# 11_INPUT.net
KiCad netlist of a schematic drawn in Altium Designer
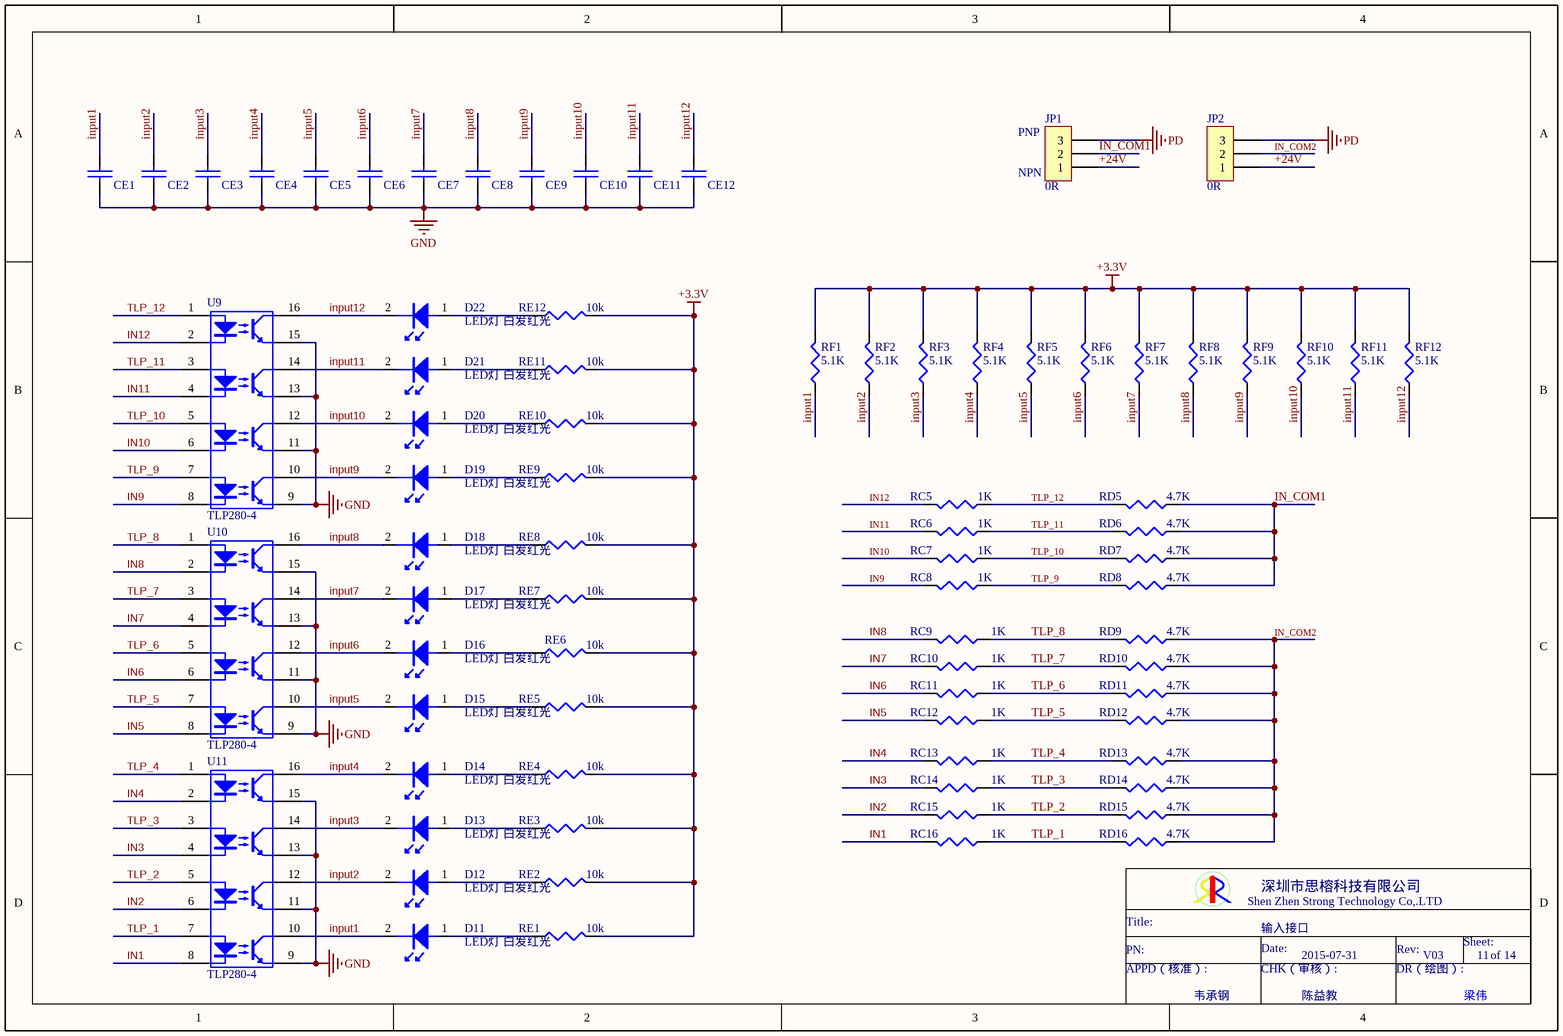
[diagram p0: 11_INPUT.SchDoc]

(export (version "E")
  (design (tool "Eeschema 10.0.6"))
  (components
    (comp (ref "CE1")
      (value "100pF")
      (footprint "0603C")
      (description "Capacitor")
      (libsource (lib "Mylibrary") (part "CAP"))
    )
    (comp (ref "CE2")
      (value "100pF")
      (footprint "0603C")
      (description "Capacitor")
      (libsource (lib "Mylibrary") (part "CAP"))
    )
    (comp (ref "CE3")
      (value "100pF")
      (footprint "0603C")
      (description "Capacitor")
      (libsource (lib "Mylibrary") (part "CAP"))
    )
    (comp (ref "CE4")
      (value "100pF")
      (footprint "0603C")
      (description "Capacitor")
      (libsource (lib "Mylibrary") (part "CAP"))
    )
    (comp (ref "CE5")
      (value "100pF")
      (footprint "0603C")
      (description "Capacitor")
      (libsource (lib "Mylibrary") (part "CAP"))
    )
    (comp (ref "CE6")
      (value "100pF")
      (footprint "0603C")
      (description "Capacitor")
      (libsource (lib "Mylibrary") (part "CAP"))
    )
    (comp (ref "CE7")
      (value "100pF")
      (footprint "0603C")
      (description "Capacitor")
      (libsource (lib "Mylibrary") (part "CAP"))
    )
    (comp (ref "CE8")
      (value "100pF")
      (footprint "0603C")
      (description "Capacitor")
      (libsource (lib "Mylibrary") (part "CAP"))
    )
    (comp (ref "CE9")
      (value "100pF")
      (footprint "0603C")
      (description "Capacitor")
      (libsource (lib "Mylibrary") (part "CAP"))
    )
    (comp (ref "CE10")
      (value "100pF")
      (footprint "0603C")
      (description "Capacitor")
      (libsource (lib "Mylibrary") (part "CAP"))
    )
    (comp (ref "CE11")
      (value "100pF")
      (footprint "0603C")
      (description "Capacitor")
      (libsource (lib "Mylibrary") (part "CAP"))
    )
    (comp (ref "CE12")
      (value "100pF")
      (footprint "0603C")
      (description "Capacitor")
      (libsource (lib "Mylibrary") (part "CAP"))
    )
    (comp (ref "D11")
      (value "LED灯 白发红光")
      (footprint "D0603")
      (description "LED灯")
      (libsource (lib "Mylibrary") (part "LED"))
    )
    (comp (ref "D12")
      (value "LED灯 白发红光")
      (footprint "D0603")
      (description "LED灯")
      (libsource (lib "Mylibrary") (part "LED"))
    )
    (comp (ref "D13")
      (value "LED灯 白发红光")
      (footprint "D0603")
      (description "LED灯")
      (libsource (lib "Mylibrary") (part "LED"))
    )
    (comp (ref "D14")
      (value "LED灯 白发红光")
      (footprint "D0603")
      (description "LED灯")
      (libsource (lib "Mylibrary") (part "LED"))
    )
    (comp (ref "D15")
      (value "LED灯 白发红光")
      (footprint "D0603")
      (description "LED灯")
      (libsource (lib "Mylibrary") (part "LED"))
    )
    (comp (ref "D16")
      (value "LED灯 白发红光")
      (footprint "D0603")
      (description "LED灯")
      (libsource (lib "Mylibrary") (part "LED"))
    )
    (comp (ref "D17")
      (value "LED灯 白发红光")
      (footprint "D0603")
      (description "LED灯")
      (libsource (lib "Mylibrary") (part "LED"))
    )
    (comp (ref "D18")
      (value "LED灯 白发红光")
      (footprint "D0603")
      (description "LED灯")
      (libsource (lib "Mylibrary") (part "LED"))
    )
    (comp (ref "D19")
      (value "LED灯 白发红光")
      (footprint "D0603")
      (description "LED灯")
      (libsource (lib "Mylibrary") (part "LED"))
    )
    (comp (ref "D20")
      (value "LED灯 白发红光")
      (footprint "D0603")
      (description "LED灯")
      (libsource (lib "Mylibrary") (part "LED"))
    )
    (comp (ref "D21")
      (value "LED灯 白发红光")
      (footprint "D0603")
      (description "LED灯")
      (libsource (lib "Mylibrary") (part "LED"))
    )
    (comp (ref "D22")
      (value "LED灯 白发红光")
      (footprint "D0603")
      (description "LED灯")
      (libsource (lib "Mylibrary") (part "LED"))
    )
    (comp (ref "JP1")
      (value "0R")
      (footprint "3*0.6")
      (description "Connector")
      (libsource (lib "Miscellaneous Devices") (part "CON3"))
    )
    (comp (ref "JP2")
      (value "0R")
      (footprint "3*0.6")
      (description "Connector")
      (libsource (lib "Miscellaneous Devices") (part "CON3"))
    )
    (comp (ref "RC5") (value "1K") (footprint "0603R") (libsource (lib "Mylibrary") (part "RES1")))
    (comp (ref "RC6") (value "1K") (footprint "0603R") (libsource (lib "Mylibrary") (part "RES1")))
    (comp (ref "RC7") (value "1K") (footprint "0603R") (libsource (lib "Mylibrary") (part "RES1")))
    (comp (ref "RC8") (value "1K") (footprint "0603R") (libsource (lib "Mylibrary") (part "RES1")))
    (comp (ref "RC9") (value "1K") (footprint "0603R") (libsource (lib "Mylibrary") (part "RES1")))
    (comp (ref "RC10") (value "1K") (footprint "0603R") (libsource (lib "Mylibrary") (part "RES1")))
    (comp (ref "RC11") (value "1K") (footprint "0603R") (libsource (lib "Mylibrary") (part "RES1")))
    (comp (ref "RC12") (value "1K") (footprint "0603R") (libsource (lib "Mylibrary") (part "RES1")))
    (comp (ref "RC13") (value "1K") (footprint "0603R") (libsource (lib "Mylibrary") (part "RES1")))
    (comp (ref "RC14") (value "1K") (footprint "0603R") (libsource (lib "Mylibrary") (part "RES1")))
    (comp (ref "RC15") (value "1K") (footprint "0603R") (libsource (lib "Mylibrary") (part "RES1")))
    (comp (ref "RC16") (value "1K") (footprint "0603R") (libsource (lib "Mylibrary") (part "RES1")))
    (comp (ref "RD5") (value "4.7K") (footprint "1206R") (libsource (lib "Mylibrary") (part "RES1")))
    (comp (ref "RD6") (value "4.7K") (footprint "1206R") (libsource (lib "Mylibrary") (part "RES1")))
    (comp (ref "RD7") (value "4.7K") (footprint "1206R") (libsource (lib "Mylibrary") (part "RES1")))
    (comp (ref "RD8") (value "4.7K") (footprint "1206R") (libsource (lib "Mylibrary") (part "RES1")))
    (comp (ref "RD9") (value "4.7K") (footprint "1206R") (libsource (lib "Mylibrary") (part "RES1")))
    (comp (ref "RD10") (value "4.7K") (footprint "1206R") (libsource (lib "Mylibrary") (part "RES1")))
    (comp (ref "RD11") (value "4.7K") (footprint "1206R") (libsource (lib "Mylibrary") (part "RES1")))
    (comp (ref "RD12") (value "4.7K") (footprint "1206R") (libsource (lib "Mylibrary") (part "RES1")))
    (comp (ref "RD13") (value "4.7K") (footprint "1206R") (libsource (lib "Mylibrary") (part "RES1")))
    (comp (ref "RD14") (value "4.7K") (footprint "1206R") (libsource (lib "Mylibrary") (part "RES1")))
    (comp (ref "RD15") (value "4.7K") (footprint "1206R") (libsource (lib "Mylibrary") (part "RES1")))
    (comp (ref "RD16") (value "4.7K") (footprint "1206R") (libsource (lib "Mylibrary") (part "RES1")))
    (comp (ref "RE1") (value "10k") (footprint "0603R") (libsource (lib "Mylibrary") (part "RES1")))
    (comp (ref "RE2") (value "10k") (footprint "0603R") (libsource (lib "Mylibrary") (part "RES1")))
    (comp (ref "RE3") (value "10k") (footprint "0603R") (libsource (lib "Mylibrary") (part "RES1")))
    (comp (ref "RE4") (value "10k") (footprint "0603R") (libsource (lib "Mylibrary") (part "RES1")))
    (comp (ref "RE5") (value "10k") (footprint "0603R") (libsource (lib "Mylibrary") (part "RES1")))
    (comp (ref "RE6") (value "10k") (footprint "0603R") (libsource (lib "Mylibrary") (part "RES1")))
    (comp (ref "RE7") (value "10k") (footprint "0603R") (libsource (lib "Mylibrary") (part "RES1")))
    (comp (ref "RE8") (value "10k") (footprint "0603R") (libsource (lib "Mylibrary") (part "RES1")))
    (comp (ref "RE9") (value "10k") (footprint "0603R") (libsource (lib "Mylibrary") (part "RES1")))
    (comp (ref "RE10") (value "10k") (footprint "0603R") (libsource (lib "Mylibrary") (part "RES1")))
    (comp (ref "RE11") (value "10k") (footprint "0603R") (libsource (lib "Mylibrary") (part "RES1")))
    (comp (ref "RE12") (value "10k") (footprint "0603R") (libsource (lib "Mylibrary") (part "RES1")))
    (comp (ref "RF1") (value "5.1K") (footprint "0603R") (libsource (lib "Mylibrary") (part "RES1")))
    (comp (ref "RF2") (value "5.1K") (footprint "0603R") (libsource (lib "Mylibrary") (part "RES1")))
    (comp (ref "RF3") (value "5.1K") (footprint "0603R") (libsource (lib "Mylibrary") (part "RES1")))
    (comp (ref "RF4") (value "5.1K") (footprint "0603R") (libsource (lib "Mylibrary") (part "RES1")))
    (comp (ref "RF5") (value "5.1K") (footprint "0603R") (libsource (lib "Mylibrary") (part "RES1")))
    (comp (ref "RF6") (value "5.1K") (footprint "0603R") (libsource (lib "Mylibrary") (part "RES1")))
    (comp (ref "RF7") (value "5.1K") (footprint "0603R") (libsource (lib "Mylibrary") (part "RES1")))
    (comp (ref "RF8") (value "5.1K") (footprint "0603R") (libsource (lib "Mylibrary") (part "RES1")))
    (comp (ref "RF9") (value "5.1K") (footprint "0603R") (libsource (lib "Mylibrary") (part "RES1")))
    (comp (ref "RF10") (value "5.1K") (footprint "0603R") (libsource (lib "Mylibrary") (part "RES1")))
    (comp (ref "RF11") (value "5.1K") (footprint "0603R") (libsource (lib "Mylibrary") (part "RES1")))
    (comp (ref "RF12") (value "5.1K") (footprint "0603R") (libsource (lib "Mylibrary") (part "RES1")))
    (comp (ref "U9") (value "TLP280-4") (footprint "SOP16") (libsource (lib "Mylibrary") (part "TLP280-4")))
    (comp (ref "U10") (value "TLP280-4") (footprint "SOP16") (libsource (lib "Mylibrary") (part "TLP280-4")))
    (comp (ref "U11") (value "TLP280-4") (footprint "SOP16") (libsource (lib "Mylibrary") (part "TLP280-4")))
  )
  (nets
    (net (code "1") (name "+3.3V") (class "Default")
      (node (ref "RE1") (pin "2") (pinfunction "2_2") (pintype "passive"))
      (node (ref "RE10") (pin "1") (pinfunction "1_1") (pintype "passive"))
      (node (ref "RE11") (pin "1") (pinfunction "1_1") (pintype "passive"))
      (node (ref "RE12") (pin "1") (pinfunction "1_1") (pintype "passive"))
      (node (ref "RE2") (pin "2") (pinfunction "2_2") (pintype "passive"))
      (node (ref "RE3") (pin "2") (pinfunction "2_2") (pintype "passive"))
      (node (ref "RE4") (pin "2") (pinfunction "2_2") (pintype "passive"))
      (node (ref "RE5") (pin "2") (pinfunction "2_2") (pintype "passive"))
      (node (ref "RE6") (pin "2") (pinfunction "2_2") (pintype "passive"))
      (node (ref "RE7") (pin "2") (pinfunction "2_2") (pintype "passive"))
      (node (ref "RE8") (pin "2") (pinfunction "2_2") (pintype "passive"))
      (node (ref "RE9") (pin "1") (pinfunction "1_1") (pintype "passive"))
      (node (ref "RF1") (pin "2") (pinfunction "2_2") (pintype "passive"))
      (node (ref "RF10") (pin "2") (pinfunction "2_2") (pintype "passive"))
      (node (ref "RF11") (pin "2") (pinfunction "2_2") (pintype "passive"))
      (node (ref "RF12") (pin "2") (pinfunction "2_2") (pintype "passive"))
      (node (ref "RF2") (pin "2") (pinfunction "2_2") (pintype "passive"))
      (node (ref "RF3") (pin "2") (pinfunction "2_2") (pintype "passive"))
      (node (ref "RF4") (pin "2") (pinfunction "2_2") (pintype "passive"))
      (node (ref "RF5") (pin "2") (pinfunction "2_2") (pintype "passive"))
      (node (ref "RF6") (pin "2") (pinfunction "2_2") (pintype "passive"))
      (node (ref "RF7") (pin "2") (pinfunction "2_2") (pintype "passive"))
      (node (ref "RF8") (pin "2") (pinfunction "2_2") (pintype "passive"))
      (node (ref "RF9") (pin "2") (pinfunction "2_2") (pintype "passive"))
    )
    (net (code "2") (name "/+24V") (class "Default")
      (node (ref "JP1") (pin "1") (pinfunction "1_1") (pintype "passive"))
      (node (ref "JP2") (pin "1") (pinfunction "1_1") (pintype "passive"))
    )
    (net (code "3") (name "/IN1") (class "Default")
      (node (ref "RC16") (pin "2") (pinfunction "2_2") (pintype "passive"))
      (node (ref "U11") (pin "8") (pinfunction "LED_Cathode_8") (pintype "passive"))
    )
    (net (code "4") (name "/IN2") (class "Default")
      (node (ref "RC15") (pin "2") (pinfunction "2_2") (pintype "passive"))
      (node (ref "U11") (pin "6") (pinfunction "LED_Cathode_6") (pintype "passive"))
    )
    (net (code "5") (name "/IN3") (class "Default")
      (node (ref "RC14") (pin "2") (pinfunction "2_2") (pintype "passive"))
      (node (ref "U11") (pin "4") (pinfunction "LED_Cathode_4") (pintype "passive"))
    )
    (net (code "6") (name "/IN4") (class "Default")
      (node (ref "RC13") (pin "2") (pinfunction "2_2") (pintype "passive"))
      (node (ref "U11") (pin "2") (pinfunction "LED_Cathode_2") (pintype "passive"))
    )
    (net (code "7") (name "/IN5") (class "Default")
      (node (ref "RC12") (pin "2") (pinfunction "2_2") (pintype "passive"))
      (node (ref "U10") (pin "8") (pinfunction "LED_Cathode_8") (pintype "passive"))
    )
    (net (code "8") (name "/IN6") (class "Default")
      (node (ref "RC11") (pin "2") (pinfunction "2_2") (pintype "passive"))
      (node (ref "U10") (pin "6") (pinfunction "LED_Cathode_6") (pintype "passive"))
    )
    (net (code "9") (name "/IN7") (class "Default")
      (node (ref "RC10") (pin "2") (pinfunction "2_2") (pintype "passive"))
      (node (ref "U10") (pin "4") (pinfunction "LED_Cathode_4") (pintype "passive"))
    )
    (net (code "10") (name "/IN8") (class "Default")
      (node (ref "RC9") (pin "2") (pinfunction "2_2") (pintype "passive"))
      (node (ref "U10") (pin "2") (pinfunction "LED_Cathode_2") (pintype "passive"))
    )
    (net (code "11") (name "/IN9") (class "Default")
      (node (ref "RC8") (pin "2") (pinfunction "2_2") (pintype "passive"))
      (node (ref "U9") (pin "8") (pinfunction "LED_Cathode_8") (pintype "passive"))
    )
    (net (code "12") (name "/IN10") (class "Default")
      (node (ref "RC7") (pin "2") (pinfunction "2_2") (pintype "passive"))
      (node (ref "U9") (pin "6") (pinfunction "LED_Cathode_6") (pintype "passive"))
    )
    (net (code "13") (name "/IN11") (class "Default")
      (node (ref "RC6") (pin "2") (pinfunction "2_2") (pintype "passive"))
      (node (ref "U9") (pin "4") (pinfunction "LED_Cathode_4") (pintype "passive"))
    )
    (net (code "14") (name "/IN12") (class "Default")
      (node (ref "RC5") (pin "2") (pinfunction "2_2") (pintype "passive"))
      (node (ref "U9") (pin "2") (pinfunction "LED_Cathode_2") (pintype "passive"))
    )
    (net (code "15") (name "/IN_COM1") (class "Default")
      (node (ref "JP1") (pin "2") (pinfunction "2_2") (pintype "passive"))
      (node (ref "RD5") (pin "1") (pinfunction "1_1") (pintype "passive"))
      (node (ref "RD6") (pin "1") (pinfunction "1_1") (pintype "passive"))
      (node (ref "RD7") (pin "1") (pinfunction "1_1") (pintype "passive"))
      (node (ref "RD8") (pin "1") (pinfunction "1_1") (pintype "passive"))
    )
    (net (code "16") (name "/IN_COM2") (class "Default")
      (node (ref "JP2") (pin "2") (pinfunction "2_2") (pintype "passive"))
      (node (ref "RD10") (pin "1") (pinfunction "1_1") (pintype "passive"))
      (node (ref "RD11") (pin "1") (pinfunction "1_1") (pintype "passive"))
      (node (ref "RD12") (pin "1") (pinfunction "1_1") (pintype "passive"))
      (node (ref "RD13") (pin "1") (pinfunction "1_1") (pintype "passive"))
      (node (ref "RD14") (pin "1") (pinfunction "1_1") (pintype "passive"))
      (node (ref "RD15") (pin "1") (pinfunction "1_1") (pintype "passive"))
      (node (ref "RD16") (pin "1") (pinfunction "1_1") (pintype "passive"))
      (node (ref "RD9") (pin "1") (pinfunction "1_1") (pintype "passive"))
    )
    (net (code "17") (name "/TLP_1") (class "Default")
      (node (ref "RC16") (pin "1") (pinfunction "1_1") (pintype "passive"))
      (node (ref "RD16") (pin "2") (pinfunction "2_2") (pintype "passive"))
      (node (ref "U11") (pin "7") (pinfunction "LED_Anode_7") (pintype "passive"))
    )
    (net (code "18") (name "/TLP_2") (class "Default")
      (node (ref "RC15") (pin "1") (pinfunction "1_1") (pintype "passive"))
      (node (ref "RD15") (pin "2") (pinfunction "2_2") (pintype "passive"))
      (node (ref "U11") (pin "5") (pinfunction "LED_Anode_5") (pintype "passive"))
    )
    (net (code "19") (name "/TLP_3") (class "Default")
      (node (ref "RC14") (pin "1") (pinfunction "1_1") (pintype "passive"))
      (node (ref "RD14") (pin "2") (pinfunction "2_2") (pintype "passive"))
      (node (ref "U11") (pin "3") (pinfunction "LED_Anode_3") (pintype "passive"))
    )
    (net (code "20") (name "/TLP_4") (class "Default")
      (node (ref "RC13") (pin "1") (pinfunction "1_1") (pintype "passive"))
      (node (ref "RD13") (pin "2") (pinfunction "2_2") (pintype "passive"))
      (node (ref "U11") (pin "1") (pinfunction "LED_Anode_1") (pintype "passive"))
    )
    (net (code "21") (name "/TLP_5") (class "Default")
      (node (ref "RC12") (pin "1") (pinfunction "1_1") (pintype "passive"))
      (node (ref "RD12") (pin "2") (pinfunction "2_2") (pintype "passive"))
      (node (ref "U10") (pin "7") (pinfunction "LED_Anode_7") (pintype "passive"))
    )
    (net (code "22") (name "/TLP_6") (class "Default")
      (node (ref "RC11") (pin "1") (pinfunction "1_1") (pintype "passive"))
      (node (ref "RD11") (pin "2") (pinfunction "2_2") (pintype "passive"))
      (node (ref "U10") (pin "5") (pinfunction "LED_Anode_5") (pintype "passive"))
    )
    (net (code "23") (name "/TLP_7") (class "Default")
      (node (ref "RC10") (pin "1") (pinfunction "1_1") (pintype "passive"))
      (node (ref "RD10") (pin "2") (pinfunction "2_2") (pintype "passive"))
      (node (ref "U10") (pin "3") (pinfunction "LED_Anode_3") (pintype "passive"))
    )
    (net (code "24") (name "/TLP_8") (class "Default")
      (node (ref "RC9") (pin "1") (pinfunction "1_1") (pintype "passive"))
      (node (ref "RD9") (pin "2") (pinfunction "2_2") (pintype "passive"))
      (node (ref "U10") (pin "1") (pinfunction "LED_Anode_1") (pintype "passive"))
    )
    (net (code "25") (name "/TLP_9") (class "Default")
      (node (ref "RC8") (pin "1") (pinfunction "1_1") (pintype "passive"))
      (node (ref "RD8") (pin "2") (pinfunction "2_2") (pintype "passive"))
      (node (ref "U9") (pin "7") (pinfunction "LED_Anode_7") (pintype "passive"))
    )
    (net (code "26") (name "/TLP_10") (class "Default")
      (node (ref "RC7") (pin "1") (pinfunction "1_1") (pintype "passive"))
      (node (ref "RD7") (pin "2") (pinfunction "2_2") (pintype "passive"))
      (node (ref "U9") (pin "5") (pinfunction "LED_Anode_5") (pintype "passive"))
    )
    (net (code "27") (name "/TLP_11") (class "Default")
      (node (ref "RC6") (pin "1") (pinfunction "1_1") (pintype "passive"))
      (node (ref "RD6") (pin "2") (pinfunction "2_2") (pintype "passive"))
      (node (ref "U9") (pin "3") (pinfunction "LED_Anode_3") (pintype "passive"))
    )
    (net (code "28") (name "/TLP_12") (class "Default")
      (node (ref "RC5") (pin "1") (pinfunction "1_1") (pintype "passive"))
      (node (ref "RD5") (pin "2") (pinfunction "2_2") (pintype "passive"))
      (node (ref "U9") (pin "1") (pinfunction "LED_Anode_1") (pintype "passive"))
    )
    (net (code "29") (name "/input1") (class "Default")
      (node (ref "CE1") (pin "1") (pinfunction "1_1") (pintype "passive"))
      (node (ref "D11") (pin "2") (pinfunction "2_2") (pintype "passive"))
      (node (ref "RF1") (pin "1") (pinfunction "1_1") (pintype "passive"))
      (node (ref "U11") (pin "10") (pinfunction "Collector_10") (pintype "passive"))
    )
    (net (code "30") (name "/input2") (class "Default")
      (node (ref "CE2") (pin "1") (pinfunction "1_1") (pintype "passive"))
      (node (ref "D12") (pin "2") (pinfunction "2_2") (pintype "passive"))
      (node (ref "RF2") (pin "1") (pinfunction "1_1") (pintype "passive"))
      (node (ref "U11") (pin "12") (pinfunction "Collector_12") (pintype "passive"))
    )
    (net (code "31") (name "/input3") (class "Default")
      (node (ref "CE3") (pin "1") (pinfunction "1_1") (pintype "passive"))
      (node (ref "D13") (pin "2") (pinfunction "2_2") (pintype "passive"))
      (node (ref "RF3") (pin "1") (pinfunction "1_1") (pintype "passive"))
      (node (ref "U11") (pin "14") (pinfunction "Collector_14") (pintype "passive"))
    )
    (net (code "32") (name "/input4") (class "Default")
      (node (ref "CE4") (pin "1") (pinfunction "1_1") (pintype "passive"))
      (node (ref "D14") (pin "2") (pinfunction "2_2") (pintype "passive"))
      (node (ref "RF4") (pin "1") (pinfunction "1_1") (pintype "passive"))
      (node (ref "U11") (pin "16") (pinfunction "Collector_16") (pintype "passive"))
    )
    (net (code "33") (name "/input5") (class "Default")
      (node (ref "CE5") (pin "1") (pinfunction "1_1") (pintype "passive"))
      (node (ref "D15") (pin "2") (pinfunction "2_2") (pintype "passive"))
      (node (ref "RF5") (pin "1") (pinfunction "1_1") (pintype "passive"))
      (node (ref "U10") (pin "10") (pinfunction "Collector_10") (pintype "passive"))
    )
    (net (code "34") (name "/input6") (class "Default")
      (node (ref "CE6") (pin "1") (pinfunction "1_1") (pintype "passive"))
      (node (ref "D16") (pin "2") (pinfunction "2_2") (pintype "passive"))
      (node (ref "RF6") (pin "1") (pinfunction "1_1") (pintype "passive"))
      (node (ref "U10") (pin "12") (pinfunction "Collector_12") (pintype "passive"))
    )
    (net (code "35") (name "/input7") (class "Default")
      (node (ref "CE7") (pin "1") (pinfunction "1_1") (pintype "passive"))
      (node (ref "D17") (pin "2") (pinfunction "2_2") (pintype "passive"))
      (node (ref "RF7") (pin "1") (pinfunction "1_1") (pintype "passive"))
      (node (ref "U10") (pin "14") (pinfunction "Collector_14") (pintype "passive"))
    )
    (net (code "36") (name "/input8") (class "Default")
      (node (ref "CE8") (pin "1") (pinfunction "1_1") (pintype "passive"))
      (node (ref "D18") (pin "2") (pinfunction "2_2") (pintype "passive"))
      (node (ref "RF8") (pin "1") (pinfunction "1_1") (pintype "passive"))
      (node (ref "U10") (pin "16") (pinfunction "Collector_16") (pintype "passive"))
    )
    (net (code "37") (name "/input9") (class "Default")
      (node (ref "CE9") (pin "1") (pinfunction "1_1") (pintype "passive"))
      (node (ref "D19") (pin "2") (pinfunction "2_2") (pintype "passive"))
      (node (ref "RF9") (pin "1") (pinfunction "1_1") (pintype "passive"))
      (node (ref "U9") (pin "10") (pinfunction "Collector_10") (pintype "passive"))
    )
    (net (code "38") (name "/input10") (class "Default")
      (node (ref "CE10") (pin "1") (pinfunction "1_1") (pintype "passive"))
      (node (ref "D20") (pin "2") (pinfunction "2_2") (pintype "passive"))
      (node (ref "RF10") (pin "1") (pinfunction "1_1") (pintype "passive"))
      (node (ref "U9") (pin "12") (pinfunction "Collector_12") (pintype "passive"))
    )
    (net (code "39") (name "/input11") (class "Default")
      (node (ref "CE11") (pin "1") (pinfunction "1_1") (pintype "passive"))
      (node (ref "D21") (pin "2") (pinfunction "2_2") (pintype "passive"))
      (node (ref "RF11") (pin "1") (pinfunction "1_1") (pintype "passive"))
      (node (ref "U9") (pin "14") (pinfunction "Collector_14") (pintype "passive"))
    )
    (net (code "40") (name "/input12") (class "Default")
      (node (ref "CE12") (pin "1") (pinfunction "1_1") (pintype "passive"))
      (node (ref "D22") (pin "2") (pinfunction "2_2") (pintype "passive"))
      (node (ref "RF12") (pin "1") (pinfunction "1_1") (pintype "passive"))
      (node (ref "U9") (pin "16") (pinfunction "Collector_16") (pintype "passive"))
    )
    (net (code "41") (name "GND") (class "Default")
      (node (ref "CE1") (pin "2") (pinfunction "2_2") (pintype "passive"))
      (node (ref "CE10") (pin "2") (pinfunction "2_2") (pintype "passive"))
      (node (ref "CE11") (pin "2") (pinfunction "2_2") (pintype "passive"))
      (node (ref "CE12") (pin "2") (pinfunction "2_2") (pintype "passive"))
      (node (ref "CE2") (pin "2") (pinfunction "2_2") (pintype "passive"))
      (node (ref "CE3") (pin "2") (pinfunction "2_2") (pintype "passive"))
      (node (ref "CE4") (pin "2") (pinfunction "2_2") (pintype "passive"))
      (node (ref "CE5") (pin "2") (pinfunction "2_2") (pintype "passive"))
      (node (ref "CE6") (pin "2") (pinfunction "2_2") (pintype "passive"))
      (node (ref "CE7") (pin "2") (pinfunction "2_2") (pintype "passive"))
      (node (ref "CE8") (pin "2") (pinfunction "2_2") (pintype "passive"))
      (node (ref "CE9") (pin "2") (pinfunction "2_2") (pintype "passive"))
      (node (ref "U10") (pin "11") (pinfunction "Emitter_11") (pintype "passive"))
      (node (ref "U10") (pin "13") (pinfunction "Emitter_13") (pintype "passive"))
      (node (ref "U10") (pin "15") (pinfunction "Emitter_15") (pintype "passive"))
      (node (ref "U10") (pin "9") (pinfunction "Emitter_9") (pintype "passive"))
      (node (ref "U11") (pin "11") (pinfunction "Emitter_11") (pintype "passive"))
      (node (ref "U11") (pin "13") (pinfunction "Emitter_13") (pintype "passive"))
      (node (ref "U11") (pin "15") (pinfunction "Emitter_15") (pintype "passive"))
      (node (ref "U11") (pin "9") (pinfunction "Emitter_9") (pintype "passive"))
      (node (ref "U9") (pin "11") (pinfunction "Emitter_11") (pintype "passive"))
      (node (ref "U9") (pin "13") (pinfunction "Emitter_13") (pintype "passive"))
      (node (ref "U9") (pin "15") (pinfunction "Emitter_15") (pintype "passive"))
      (node (ref "U9") (pin "9") (pinfunction "Emitter_9") (pintype "passive"))
    )
    (net (code "42") (name "Net-(D11-Pad1)") (class "Default")
      (node (ref "D11") (pin "1") (pinfunction "1_1") (pintype "passive"))
      (node (ref "RE1") (pin "1") (pinfunction "1_1") (pintype "passive"))
    )
    (net (code "43") (name "Net-(D12-Pad1)") (class "Default")
      (node (ref "D12") (pin "1") (pinfunction "1_1") (pintype "passive"))
      (node (ref "RE2") (pin "1") (pinfunction "1_1") (pintype "passive"))
    )
    (net (code "44") (name "Net-(D13-Pad1)") (class "Default")
      (node (ref "D13") (pin "1") (pinfunction "1_1") (pintype "passive"))
      (node (ref "RE3") (pin "1") (pinfunction "1_1") (pintype "passive"))
    )
    (net (code "45") (name "Net-(D14-Pad1)") (class "Default")
      (node (ref "D14") (pin "1") (pinfunction "1_1") (pintype "passive"))
      (node (ref "RE4") (pin "1") (pinfunction "1_1") (pintype "passive"))
    )
    (net (code "46") (name "Net-(D15-Pad1)") (class "Default")
      (node (ref "D15") (pin "1") (pinfunction "1_1") (pintype "passive"))
      (node (ref "RE5") (pin "1") (pinfunction "1_1") (pintype "passive"))
    )
    (net (code "47") (name "Net-(D16-Pad1)") (class "Default")
      (node (ref "D16") (pin "1") (pinfunction "1_1") (pintype "passive"))
      (node (ref "RE6") (pin "1") (pinfunction "1_1") (pintype "passive"))
    )
    (net (code "48") (name "Net-(D17-Pad1)") (class "Default")
      (node (ref "D17") (pin "1") (pinfunction "1_1") (pintype "passive"))
      (node (ref "RE7") (pin "1") (pinfunction "1_1") (pintype "passive"))
    )
    (net (code "49") (name "Net-(D18-Pad1)") (class "Default")
      (node (ref "D18") (pin "1") (pinfunction "1_1") (pintype "passive"))
      (node (ref "RE8") (pin "1") (pinfunction "1_1") (pintype "passive"))
    )
    (net (code "50") (name "Net-(D19-Pad1)") (class "Default")
      (node (ref "D19") (pin "1") (pinfunction "1_1") (pintype "passive"))
      (node (ref "RE9") (pin "2") (pinfunction "2_2") (pintype "passive"))
    )
    (net (code "51") (name "Net-(D20-Pad1)") (class "Default")
      (node (ref "D20") (pin "1") (pinfunction "1_1") (pintype "passive"))
      (node (ref "RE10") (pin "2") (pinfunction "2_2") (pintype "passive"))
    )
    (net (code "52") (name "Net-(D21-Pad1)") (class "Default")
      (node (ref "D21") (pin "1") (pinfunction "1_1") (pintype "passive"))
      (node (ref "RE11") (pin "2") (pinfunction "2_2") (pintype "passive"))
    )
    (net (code "53") (name "Net-(D22-Pad1)") (class "Default")
      (node (ref "D22") (pin "1") (pinfunction "1_1") (pintype "passive"))
      (node (ref "RE12") (pin "2") (pinfunction "2_2") (pintype "passive"))
    )
    (net (code "54") (name "PD") (class "Default")
      (node (ref "JP1") (pin "3") (pinfunction "3_3") (pintype "passive"))
      (node (ref "JP2") (pin "3") (pinfunction "3_3") (pintype "passive"))
    )
  )
)
